# LPCB220_-_THROTTLE_MUX_TOP.net
KiCad netlist of a schematic drawn in Altium Designer
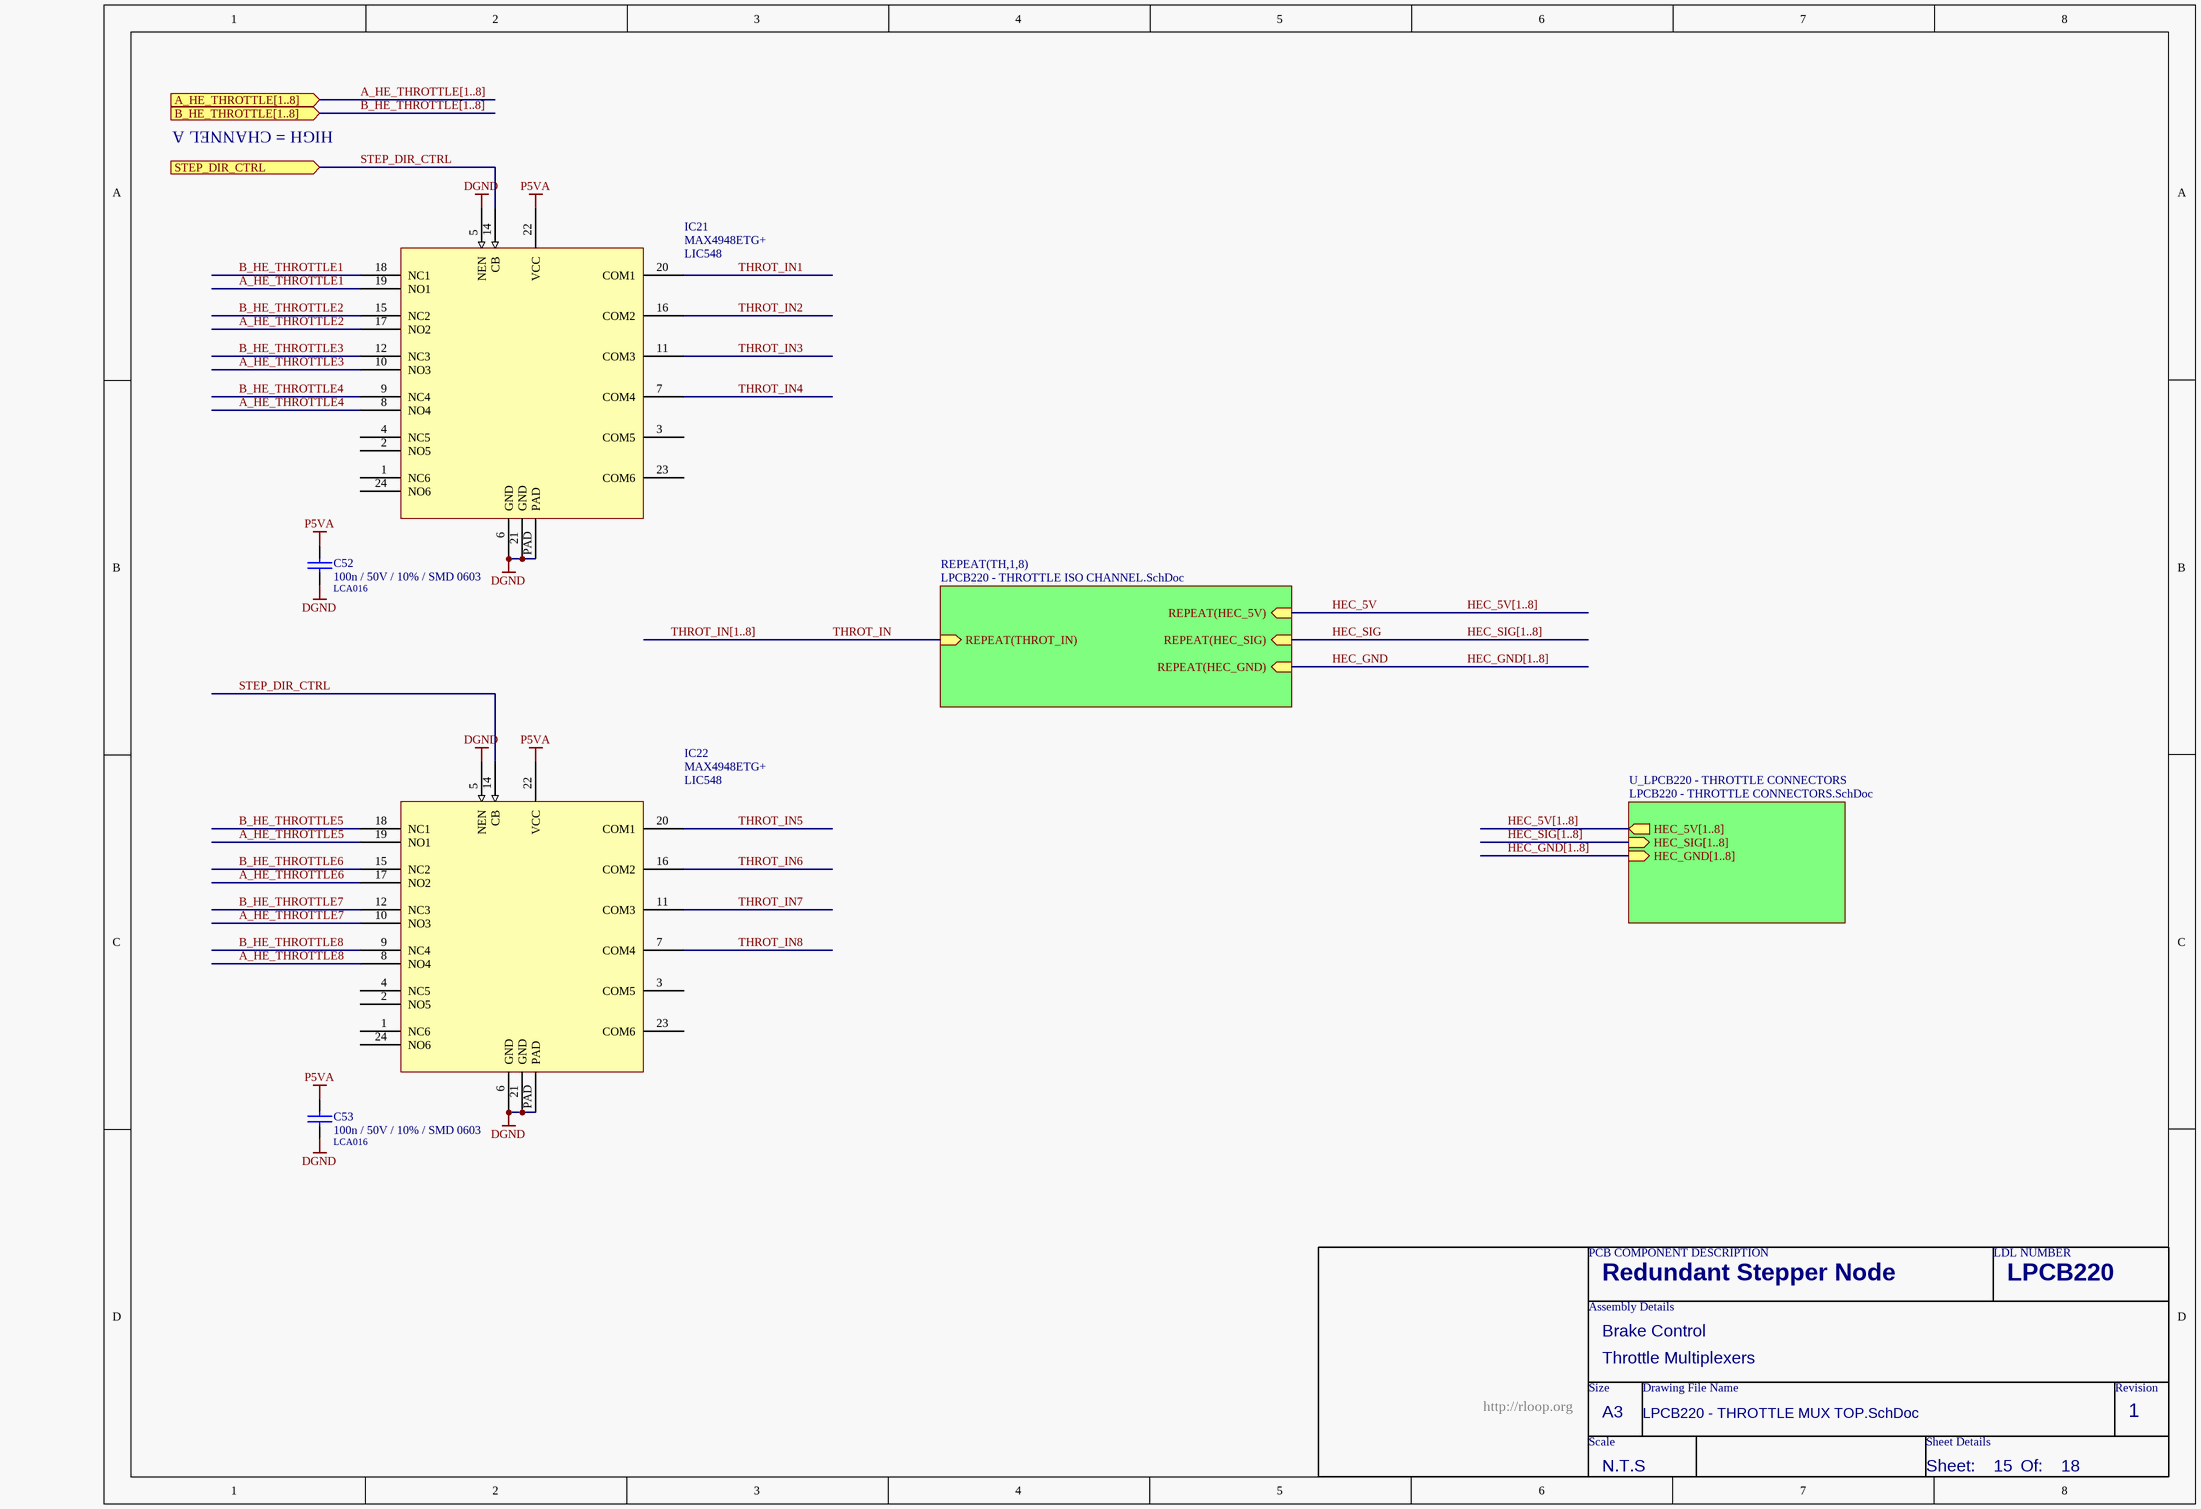
[diagram p0: LPCB220 - THROTTLE MUX TOP.SchDoc]

(export (version "E")
  (design (tool "Eeschema 10.0.6"))
  (components
    (comp (ref "C52")
      (value "100n / 50V / 10% / SMD 0603")
      (footprint "LFP011__CC1608-0603-IPC7351_B")
      (description "Capacitor, Ceramic Chip, 100nF (0.1uF), 50V, 5%, SMD 0603 [LCA016]")
      (fields (field (name "LDL_NUMBER") "LCA016"))
      (libsource (lib "LDL_Capacitors") (part "100n / 50V / 10% / SMD 0603"))
    )
    (comp (ref "C53")
      (value "100n / 50V / 10% / SMD 0603")
      (footprint "LFP011__CC1608-0603-IPC7351_B")
      (description "Capacitor, Ceramic Chip, 100nF (0.1uF), 50V, 5%, SMD 0603 [LCA016]")
      (fields (field (name "LDL_NUMBER") "LCA016"))
      (libsource (lib "LDL_Capacitors") (part "100n / 50V / 10% / SMD 0603"))
    )
    (comp (ref "IC21")
      (value "MAX4948ETG+")
      (footprint "LFP095__QFN127P600-8N")
      (description "IC, Analog Switch, SMD [LIC548]")
      (fields (field (name "LDL_NUMBER") "LIC548"))
      (libsource (lib "LDL_Semiconductors") (part "MAX4948ETG+"))
    )
    (comp (ref "IC22")
      (value "MAX4948ETG+")
      (footprint "LFP095__QFN127P600-8N")
      (description "IC, Analog Switch, SMD [LIC548]")
      (fields (field (name "LDL_NUMBER") "LIC548"))
      (libsource (lib "LDL_Semiconductors") (part "MAX4948ETG+"))
    )
  )
  (nets
    (net (code "25") (name "/A_HE_THROTTLE1") (class "Default")
      (node (ref "IC21") (pin "19") (pinfunction "NO1_19") (pintype "passive"))
    )
    (net (code "26") (name "/A_HE_THROTTLE2") (class "Default")
      (node (ref "IC21") (pin "17") (pinfunction "NO2_17") (pintype "passive"))
    )
    (net (code "27") (name "/A_HE_THROTTLE3") (class "Default")
      (node (ref "IC21") (pin "10") (pinfunction "NO3_10") (pintype "passive"))
    )
    (net (code "28") (name "/A_HE_THROTTLE4") (class "Default")
      (node (ref "IC21") (pin "8") (pinfunction "NO4_8") (pintype "passive"))
    )
    (net (code "29") (name "/A_HE_THROTTLE5") (class "Default")
      (node (ref "IC22") (pin "19") (pinfunction "NO1_19") (pintype "passive"))
    )
    (net (code "30") (name "/A_HE_THROTTLE6") (class "Default")
      (node (ref "IC22") (pin "17") (pinfunction "NO2_17") (pintype "passive"))
    )
    (net (code "31") (name "/A_HE_THROTTLE7") (class "Default")
      (node (ref "IC22") (pin "10") (pinfunction "NO3_10") (pintype "passive"))
    )
    (net (code "32") (name "/A_HE_THROTTLE8") (class "Default")
      (node (ref "IC22") (pin "8") (pinfunction "NO4_8") (pintype "passive"))
    )
    (net (code "34") (name "/B_HE_THROTTLE1") (class "Default")
      (node (ref "IC21") (pin "18") (pinfunction "NC1_18") (pintype "passive"))
    )
    (net (code "35") (name "/B_HE_THROTTLE2") (class "Default")
      (node (ref "IC21") (pin "15") (pinfunction "NC2_15") (pintype "passive"))
    )
    (net (code "36") (name "/B_HE_THROTTLE3") (class "Default")
      (node (ref "IC21") (pin "12") (pinfunction "NC3_12") (pintype "passive"))
    )
    (net (code "37") (name "/B_HE_THROTTLE4") (class "Default")
      (node (ref "IC21") (pin "9") (pinfunction "NC4_9") (pintype "passive"))
    )
    (net (code "38") (name "/B_HE_THROTTLE5") (class "Default")
      (node (ref "IC22") (pin "18") (pinfunction "NC1_18") (pintype "passive"))
    )
    (net (code "39") (name "/B_HE_THROTTLE6") (class "Default")
      (node (ref "IC22") (pin "15") (pinfunction "NC2_15") (pintype "passive"))
    )
    (net (code "40") (name "/B_HE_THROTTLE7") (class "Default")
      (node (ref "IC22") (pin "12") (pinfunction "NC3_12") (pintype "passive"))
    )
    (net (code "41") (name "/B_HE_THROTTLE8") (class "Default")
      (node (ref "IC22") (pin "9") (pinfunction "NC4_9") (pintype "passive"))
    )
    (net (code "49") (name "/STEP_DIR_CTRL") (class "Default")
      (node (ref "IC21") (pin "14") (pinfunction "CB_14") (pintype "input"))
      (node (ref "IC22") (pin "14") (pinfunction "CB_14") (pintype "input"))
    )
    (net (code "51") (name "/THROT_IN1") (class "Default")
      (node (ref "IC21") (pin "20") (pinfunction "COM1_20") (pintype "passive"))
    )
    (net (code "52") (name "/THROT_IN2") (class "Default")
      (node (ref "IC21") (pin "16") (pinfunction "COM2_16") (pintype "passive"))
    )
    (net (code "53") (name "/THROT_IN3") (class "Default")
      (node (ref "IC21") (pin "11") (pinfunction "COM3_11") (pintype "passive"))
    )
    (net (code "54") (name "/THROT_IN4") (class "Default")
      (node (ref "IC21") (pin "7") (pinfunction "COM4_7") (pintype "passive"))
    )
    (net (code "55") (name "/THROT_IN5") (class "Default")
      (node (ref "IC22") (pin "20") (pinfunction "COM1_20") (pintype "passive"))
    )
    (net (code "56") (name "/THROT_IN6") (class "Default")
      (node (ref "IC22") (pin "16") (pinfunction "COM2_16") (pintype "passive"))
    )
    (net (code "57") (name "/THROT_IN7") (class "Default")
      (node (ref "IC22") (pin "11") (pinfunction "COM3_11") (pintype "passive"))
    )
    (net (code "58") (name "/THROT_IN8") (class "Default")
      (node (ref "IC22") (pin "7") (pinfunction "COM4_7") (pintype "passive"))
    )
    (net (code "60") (name "DGND") (class "Default")
      (node (ref "C52") (pin "2") (pintype "passive"))
      (node (ref "C53") (pin "2") (pintype "passive"))
      (node (ref "IC21") (pin "21") (pinfunction "GND_21") (pintype "power_in"))
      (node (ref "IC21") (pin "5") (pinfunction "NEN_5") (pintype "input"))
      (node (ref "IC21") (pin "6") (pinfunction "GND_6") (pintype "power_in"))
      (node (ref "IC21") (pin "PAD") (pinfunction "PAD_PAD") (pintype "power_in"))
      (node (ref "IC22") (pin "21") (pinfunction "GND_21") (pintype "power_in"))
      (node (ref "IC22") (pin "5") (pinfunction "NEN_5") (pintype "input"))
      (node (ref "IC22") (pin "6") (pinfunction "GND_6") (pintype "power_in"))
      (node (ref "IC22") (pin "PAD") (pinfunction "PAD_PAD") (pintype "power_in"))
    )
    (net (code "61") (name "P5VA") (class "Default")
      (node (ref "C52") (pin "1") (pintype "passive"))
      (node (ref "C53") (pin "1") (pintype "passive"))
      (node (ref "IC21") (pin "22") (pinfunction "VCC_22") (pintype "power_in"))
      (node (ref "IC22") (pin "22") (pinfunction "VCC_22") (pintype "power_in"))
    )
    (net (code "62") (name "unconnected-(IC21-COM5-Pad3)") (class "Default")
      (node (ref "IC21") (pin "3") (pinfunction "COM5_3") (pintype "passive"))
    )
    (net (code "63") (name "unconnected-(IC21-COM6-Pad23)") (class "Default")
      (node (ref "IC21") (pin "23") (pinfunction "COM6_23") (pintype "passive"))
    )
    (net (code "64") (name "unconnected-(IC21-NC5-Pad4)") (class "Default")
      (node (ref "IC21") (pin "4") (pinfunction "NC5_4") (pintype "passive"))
    )
    (net (code "65") (name "unconnected-(IC21-NC6-Pad1)") (class "Default")
      (node (ref "IC21") (pin "1") (pinfunction "NC6_1") (pintype "passive"))
    )
    (net (code "66") (name "unconnected-(IC21-NO5-Pad2)") (class "Default")
      (node (ref "IC21") (pin "2") (pinfunction "NO5_2") (pintype "passive"))
    )
    (net (code "67") (name "unconnected-(IC21-NO6-Pad24)") (class "Default")
      (node (ref "IC21") (pin "24") (pinfunction "NO6_24") (pintype "passive"))
    )
    (net (code "68") (name "unconnected-(IC22-COM5-Pad3)") (class "Default")
      (node (ref "IC22") (pin "3") (pinfunction "COM5_3") (pintype "passive"))
    )
    (net (code "69") (name "unconnected-(IC22-COM6-Pad23)") (class "Default")
      (node (ref "IC22") (pin "23") (pinfunction "COM6_23") (pintype "passive"))
    )
    (net (code "70") (name "unconnected-(IC22-NC5-Pad4)") (class "Default")
      (node (ref "IC22") (pin "4") (pinfunction "NC5_4") (pintype "passive"))
    )
    (net (code "71") (name "unconnected-(IC22-NC6-Pad1)") (class "Default")
      (node (ref "IC22") (pin "1") (pinfunction "NC6_1") (pintype "passive"))
    )
    (net (code "72") (name "unconnected-(IC22-NO5-Pad2)") (class "Default")
      (node (ref "IC22") (pin "2") (pinfunction "NO5_2") (pintype "passive"))
    )
    (net (code "73") (name "unconnected-(IC22-NO6-Pad24)") (class "Default")
      (node (ref "IC22") (pin "24") (pinfunction "NO6_24") (pintype "passive"))
    )
  )
)
